# BIRDS-5_FM_-Y_Panel_Ver2.net
KiCad netlist of a schematic drawn in EAGLE
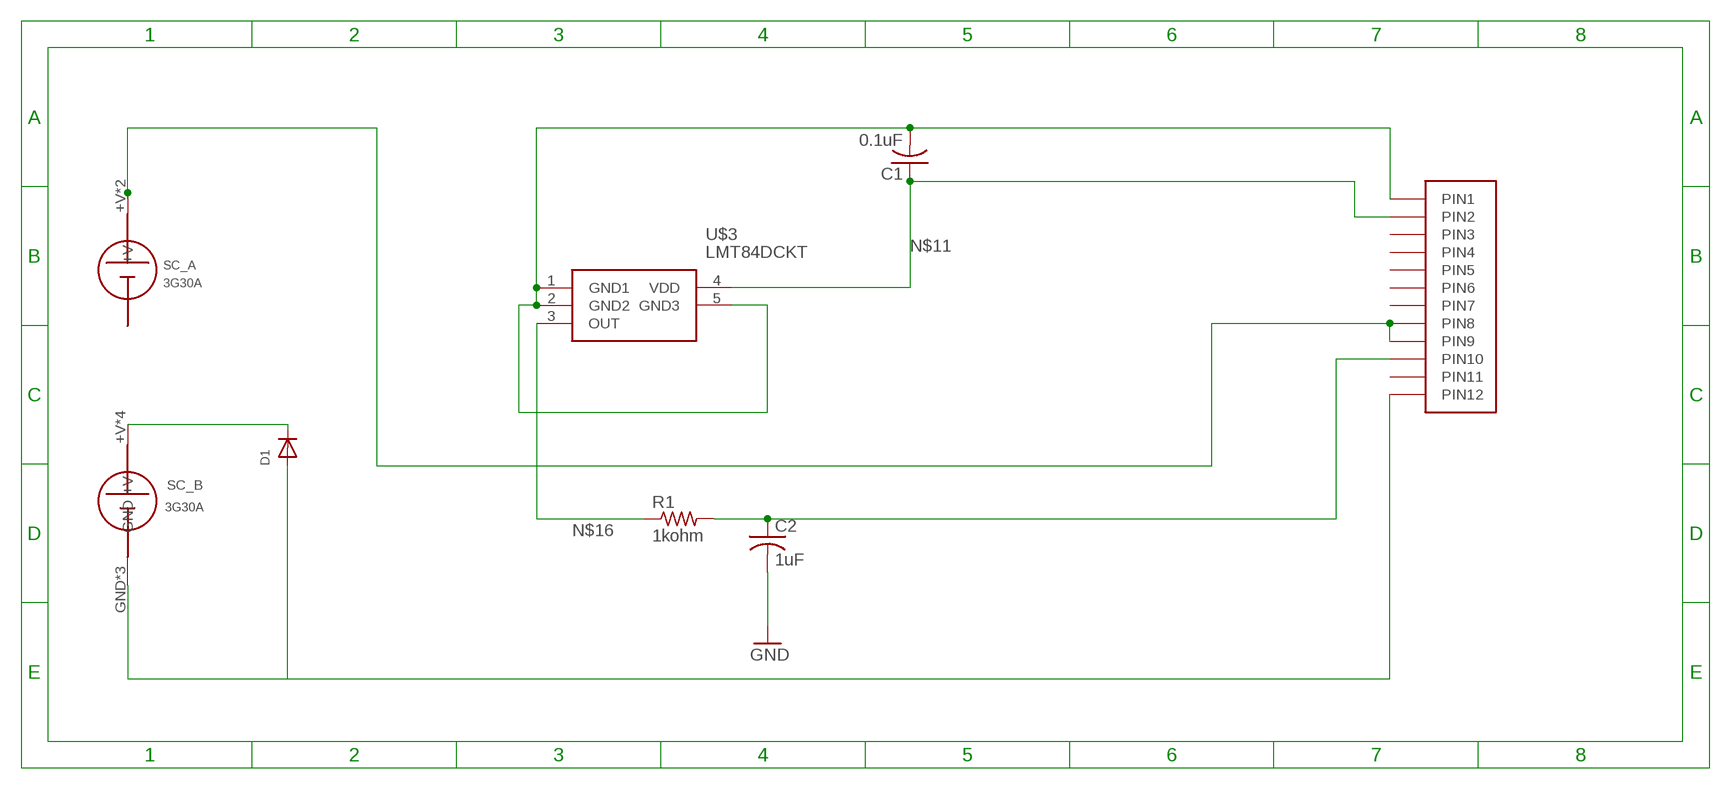
[diagram p0: schematic, sheet 1]

(export (version "E")
  (design (tool "Eeschema 10.0.6"))
  (components
    (comp (ref "C1")
      (value "0.1uF")
      (footprint "eagle-import:C0805")
      (libsource (lib "eagle-import") (part "C-USC0805"))
    )
    (comp (ref "C2")
      (value "1uF")
      (footprint "eagle-import:C0805")
      (libsource (lib "eagle-import") (part "C-USC0805"))
    )
    (comp (ref "D1")
      (value "DIODE_SOD-123FL")
      (footprint "eagle-import:SOD-123FL")
      (libsource (lib "eagle-import") (part "DIODE_SOD-123FL"))
    )
    (comp (ref "R1")
      (value "1kohm")
      (footprint "eagle-import:R0402")
      (libsource (lib "eagle-import") (part "R-US_R0402"))
    )
    (comp (ref "SOLARCELL_A")
      (value "SC_A_SC_A")
      (footprint "eagle-import:SC_A_SC_A")
      (libsource (lib "eagle-import") (part "SC_A_SC_A"))
    )
    (comp (ref "U$1")
      (value "HEADER12PIN")
      (footprint "eagle-import:HEADER12PIN")
      (libsource (lib "eagle-import") (part "HEADER12PIN"))
    )
    (comp (ref "U$2")
      (value "SC_B-2_SC_B")
      (footprint "eagle-import:SC_B-2_SC_B")
      (libsource (lib "eagle-import") (part "SC_B-2_SC_B"))
    )
    (comp (ref "U$3")
      (value "LMT84DCKT")
      (footprint "eagle-import:SOT65P210X110-5N")
      (fields (field (name "RS_PART_NUMBER") "8115860"))
      (libsource (lib "eagle-import") (part "LMT84DCKT"))
    )
  )
  (nets
    (net (code "1") (name "/N$11") (class "Default")
      (node (ref "C1") (pin "1") (pinfunction "1_1") (pintype "passive"))
      (node (ref "U$1") (pin "P2") (pinfunction "PIN2_P2") (pintype "bidirectional"))
      (node (ref "U$3") (pin "4") (pinfunction "VDD_4") (pintype "power_in"))
    )
    (net (code "2") (name "/N$16") (class "Default")
      (node (ref "R1") (pin "1") (pinfunction "1_1") (pintype "passive"))
      (node (ref "U$3") (pin "3") (pinfunction "OUT_3") (pintype "output"))
    )
    (net (code "3") (name "GND") (class "Default")
      (node (ref "C1") (pin "2") (pinfunction "2_2") (pintype "passive"))
      (node (ref "C2") (pin "2") (pinfunction "2_2") (pintype "passive"))
      (node (ref "D1") (pin "A") (pinfunction "A_A") (pintype "passive"))
      (node (ref "U$1") (pin "P1") (pinfunction "PIN1_P1") (pintype "bidirectional"))
      (node (ref "U$1") (pin "P12") (pinfunction "PIN12_P12") (pintype "bidirectional"))
      (node (ref "U$2") (pin "GND") (pinfunction "GND_GND") (pintype "bidirectional"))
      (node (ref "U$2") (pin "GND1") (pinfunction "GND_GND1") (pintype "bidirectional"))
      (node (ref "U$2") (pin "GND2") (pinfunction "GND_GND2") (pintype "bidirectional"))
      (node (ref "U$3") (pin "1") (pinfunction "GND1_1") (pintype "power_in"))
      (node (ref "U$3") (pin "2") (pinfunction "GND2_2") (pintype "power_in"))
      (node (ref "U$3") (pin "5") (pinfunction "GND3_5") (pintype "power_in"))
    )
    (net (code "4") (name "Net-(D1-PadC)") (class "Default")
      (node (ref "D1") (pin "C") (pinfunction "C_C") (pintype "passive"))
      (node (ref "U$2") (pin "+V") (pinfunction "+V_+V") (pintype "bidirectional"))
      (node (ref "U$2") (pin "+V2") (pinfunction "+V_+V2") (pintype "bidirectional"))
      (node (ref "U$2") (pin "+V3") (pinfunction "+V_+V3") (pintype "bidirectional"))
      (node (ref "U$2") (pin "+V4") (pinfunction "+V_+V4") (pintype "bidirectional"))
    )
    (net (code "5") (name "Net-(U$1-PIN8)") (class "Default")
      (node (ref "SOLARCELL_A") (pin "+V") (pinfunction "+V_+V") (pintype "bidirectional"))
      (node (ref "SOLARCELL_A") (pin "+V1") (pinfunction "+V_+V1") (pintype "bidirectional"))
      (node (ref "U$1") (pin "P8") (pinfunction "PIN8_P8") (pintype "bidirectional"))
      (node (ref "U$1") (pin "P9") (pinfunction "PIN9_P9") (pintype "bidirectional"))
    )
    (net (code "6") (name "Net-(U$1-PIN10)") (class "Default")
      (node (ref "C2") (pin "1") (pinfunction "1_1") (pintype "passive"))
      (node (ref "R1") (pin "2") (pinfunction "2_2") (pintype "passive"))
      (node (ref "U$1") (pin "P10") (pinfunction "PIN10_P10") (pintype "bidirectional"))
    )
    (net (code "7") (name "unconnected-(U$1-PIN3-PadP3)") (class "Default")
      (node (ref "U$1") (pin "P3") (pinfunction "PIN3_P3") (pintype "bidirectional"))
    )
    (net (code "8") (name "unconnected-(U$1-PIN4-PadP4)") (class "Default")
      (node (ref "U$1") (pin "P4") (pinfunction "PIN4_P4") (pintype "bidirectional"))
    )
    (net (code "9") (name "unconnected-(U$1-PIN5-PadP5)") (class "Default")
      (node (ref "U$1") (pin "P5") (pinfunction "PIN5_P5") (pintype "bidirectional"))
    )
    (net (code "10") (name "unconnected-(U$1-PIN6-PadP6)") (class "Default")
      (node (ref "U$1") (pin "P6") (pinfunction "PIN6_P6") (pintype "bidirectional"))
    )
    (net (code "11") (name "unconnected-(U$1-PIN7-PadP7)") (class "Default")
      (node (ref "U$1") (pin "P7") (pinfunction "PIN7_P7") (pintype "bidirectional"))
    )
    (net (code "12") (name "unconnected-(U$1-PIN11-PadP11)") (class "Default")
      (node (ref "U$1") (pin "P11") (pinfunction "PIN11_P11") (pintype "bidirectional"))
    )
  )
)
